# gps-harness.net
KiCad netlist of a schematic drawn in EAGLE
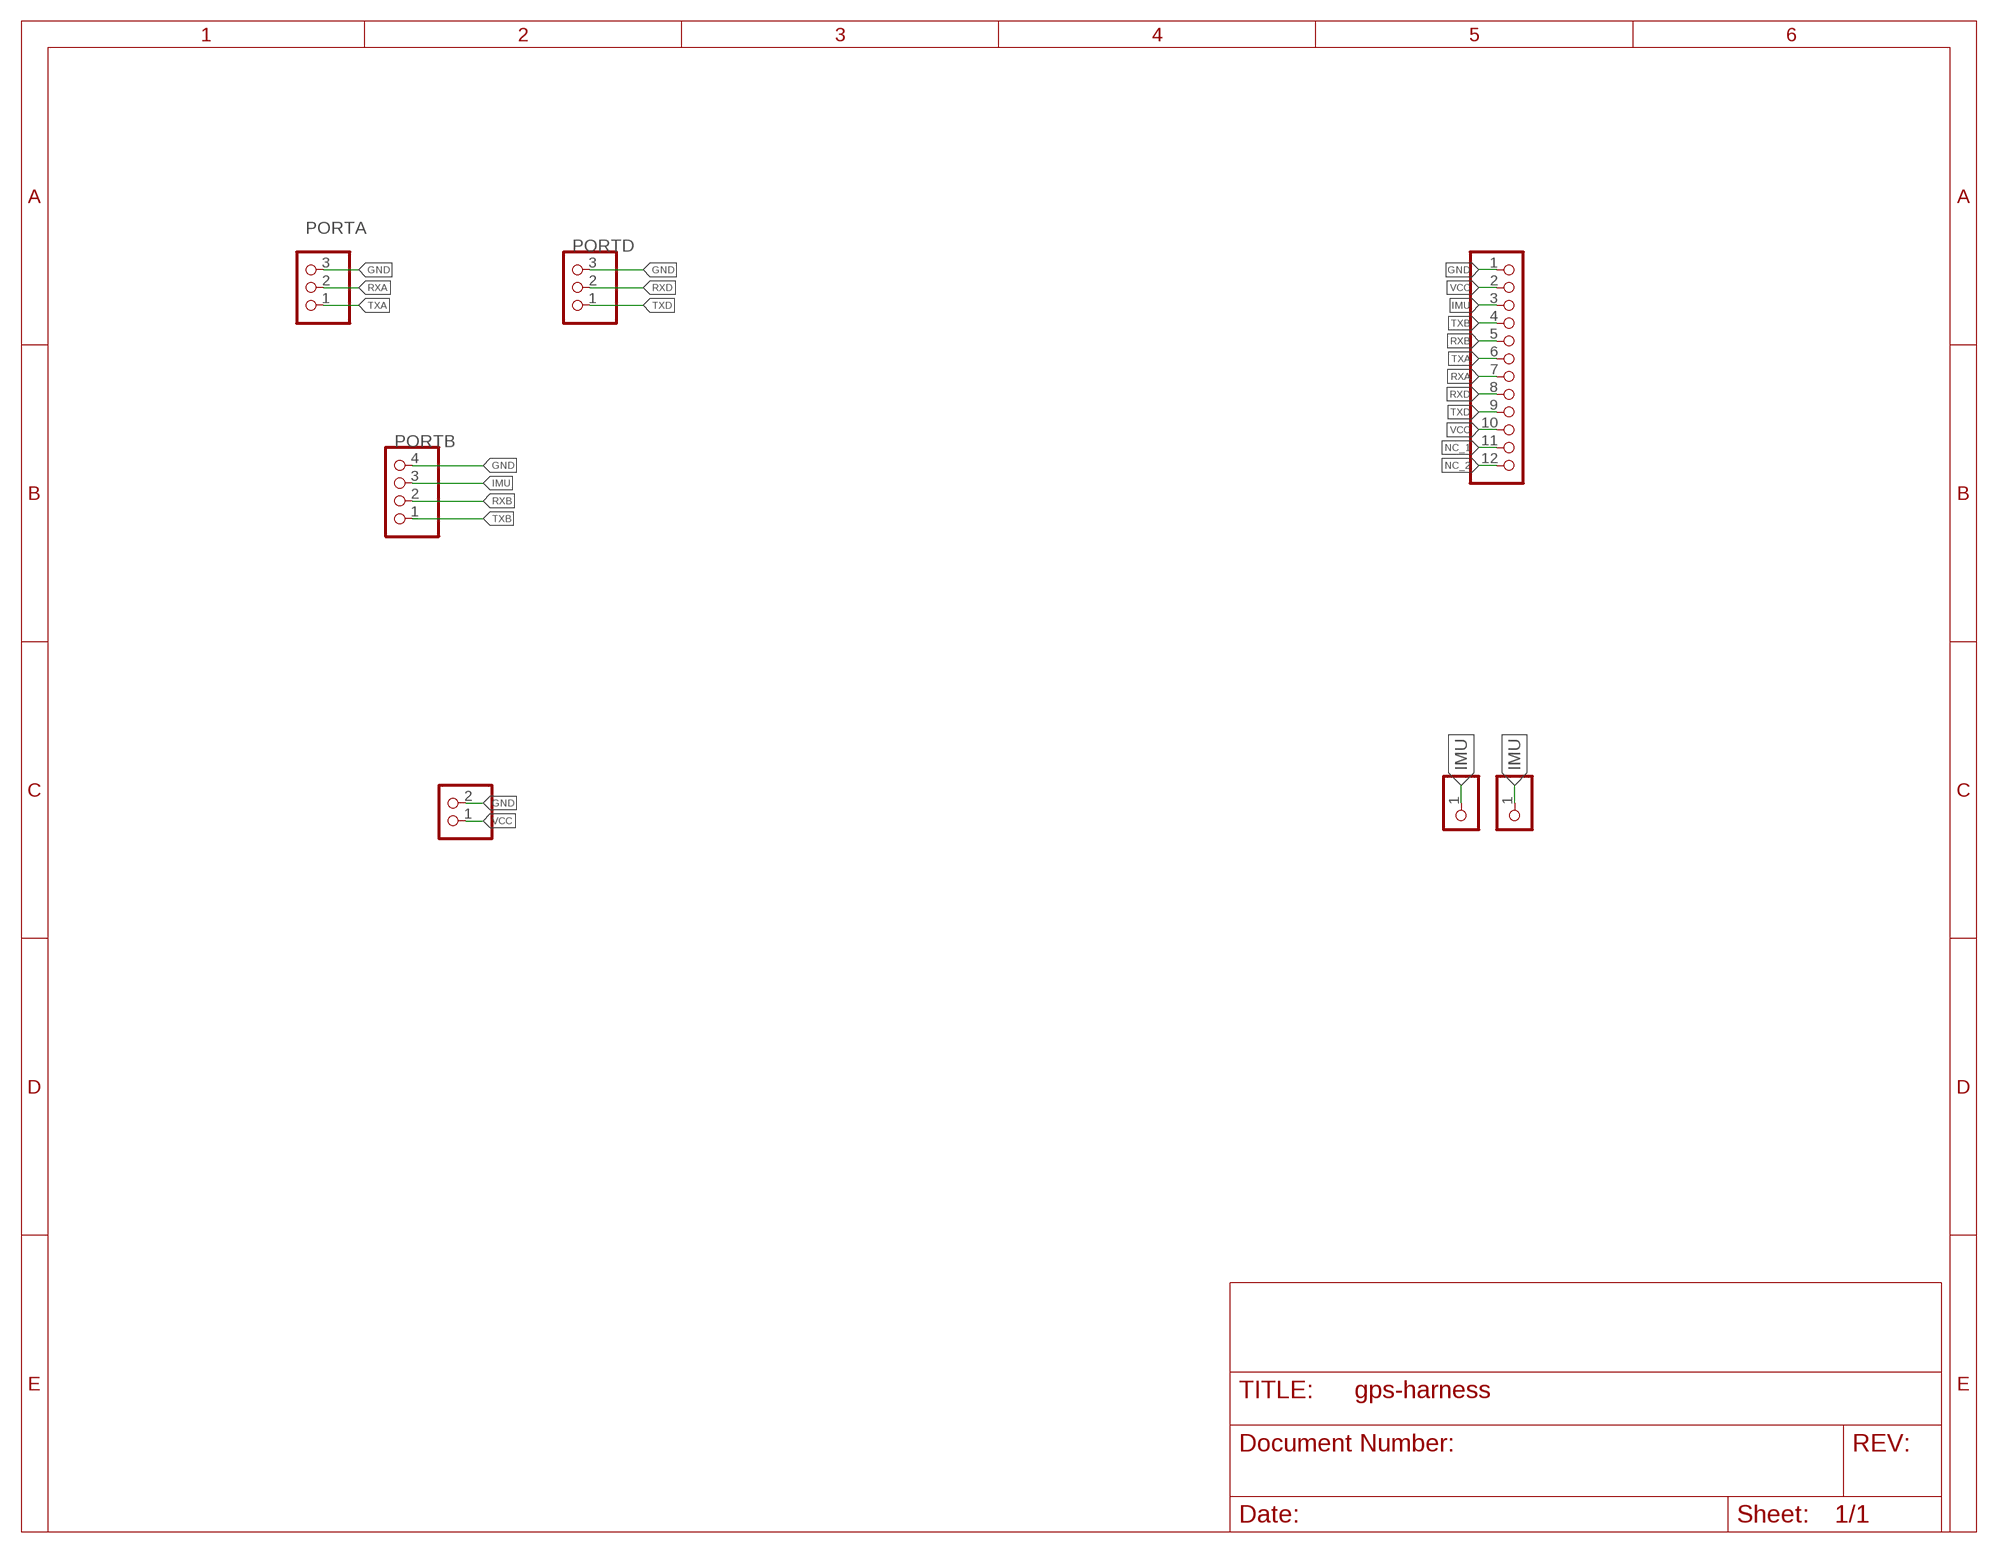
[diagram p0: schematic, sheet 1]

(export (version "E")
  (design (tool "Eeschema 10.0.6"))
  (components
    (comp (ref "BATTERY")
      (value "PINHD-1X2")
      (footprint "eagle-import:1X02")
      (libsource (lib "eagle-import") (part "PINHD-1X2"))
    )
    (comp (ref "GPIO")
      (value "PINHD-1X12")
      (footprint "eagle-import:1X12")
      (libsource (lib "eagle-import") (part "PINHD-1X12"))
    )
    (comp (ref "IMU")
      (value "PINHD-1X1")
      (footprint "eagle-import:1X01")
      (libsource (lib "eagle-import") (part "PINHD-1X1"))
    )
    (comp (ref "PORTA")
      (value "PINHD-1X3")
      (footprint "eagle-import:1X03")
      (libsource (lib "eagle-import") (part "PINHD-1X3"))
    )
    (comp (ref "PORTB")
      (value "PINHD-1X4")
      (footprint "eagle-import:1X04")
      (libsource (lib "eagle-import") (part "PINHD-1X4"))
    )
    (comp (ref "PORTD")
      (value "PINHD-1X3")
      (footprint "eagle-import:1X03")
      (libsource (lib "eagle-import") (part "PINHD-1X3"))
    )
    (comp (ref "TSY")
      (value "PINHD-1X1")
      (footprint "eagle-import:1X01")
      (libsource (lib "eagle-import") (part "PINHD-1X1"))
    )
  )
  (nets
    (net (code "1") (name "GND") (class "Default")
      (node (ref "BATTERY") (pin "2") (pinfunction "2_2") (pintype "passive"))
      (node (ref "GPIO") (pin "1") (pinfunction "1_1") (pintype "passive"))
      (node (ref "PORTA") (pin "3") (pinfunction "3_3") (pintype "passive"))
      (node (ref "PORTB") (pin "4") (pinfunction "4_4") (pintype "passive"))
      (node (ref "PORTD") (pin "3") (pinfunction "3_3") (pintype "passive"))
    )
    (net (code "2") (name "IMU") (class "Default")
      (node (ref "GPIO") (pin "3") (pinfunction "3_3") (pintype "passive"))
      (node (ref "IMU") (pin "1") (pinfunction "1_1") (pintype "passive"))
      (node (ref "PORTB") (pin "3") (pinfunction "3_3") (pintype "passive"))
      (node (ref "TSY") (pin "1") (pinfunction "1_1") (pintype "passive"))
    )
    (net (code "3") (name "NC_1") (class "Default")
      (node (ref "GPIO") (pin "11") (pinfunction "11_11") (pintype "passive"))
    )
    (net (code "4") (name "NC_2") (class "Default")
      (node (ref "GPIO") (pin "12") (pinfunction "12_12") (pintype "passive"))
    )
    (net (code "5") (name "RXA") (class "Default")
      (node (ref "GPIO") (pin "7") (pinfunction "7_7") (pintype "passive"))
      (node (ref "PORTA") (pin "2") (pinfunction "2_2") (pintype "passive"))
    )
    (net (code "6") (name "RXB") (class "Default")
      (node (ref "GPIO") (pin "5") (pinfunction "5_5") (pintype "passive"))
      (node (ref "PORTB") (pin "2") (pinfunction "2_2") (pintype "passive"))
    )
    (net (code "7") (name "RXD") (class "Default")
      (node (ref "GPIO") (pin "8") (pinfunction "8_8") (pintype "passive"))
      (node (ref "PORTD") (pin "2") (pinfunction "2_2") (pintype "passive"))
    )
    (net (code "8") (name "TXA") (class "Default")
      (node (ref "GPIO") (pin "6") (pinfunction "6_6") (pintype "passive"))
      (node (ref "PORTA") (pin "1") (pinfunction "1_1") (pintype "passive"))
    )
    (net (code "9") (name "TXB") (class "Default")
      (node (ref "GPIO") (pin "4") (pinfunction "4_4") (pintype "passive"))
      (node (ref "PORTB") (pin "1") (pinfunction "1_1") (pintype "passive"))
    )
    (net (code "10") (name "TXD") (class "Default")
      (node (ref "GPIO") (pin "9") (pinfunction "9_9") (pintype "passive"))
      (node (ref "PORTD") (pin "1") (pinfunction "1_1") (pintype "passive"))
    )
    (net (code "11") (name "VCC") (class "Default")
      (node (ref "BATTERY") (pin "1") (pinfunction "1_1") (pintype "passive"))
      (node (ref "GPIO") (pin "10") (pinfunction "10_10") (pintype "passive"))
      (node (ref "GPIO") (pin "2") (pinfunction "2_2") (pintype "passive"))
    )
  )
)
